# ASP_LEDBoard.net
KiCad netlist of a schematic drawn in Altium Designer
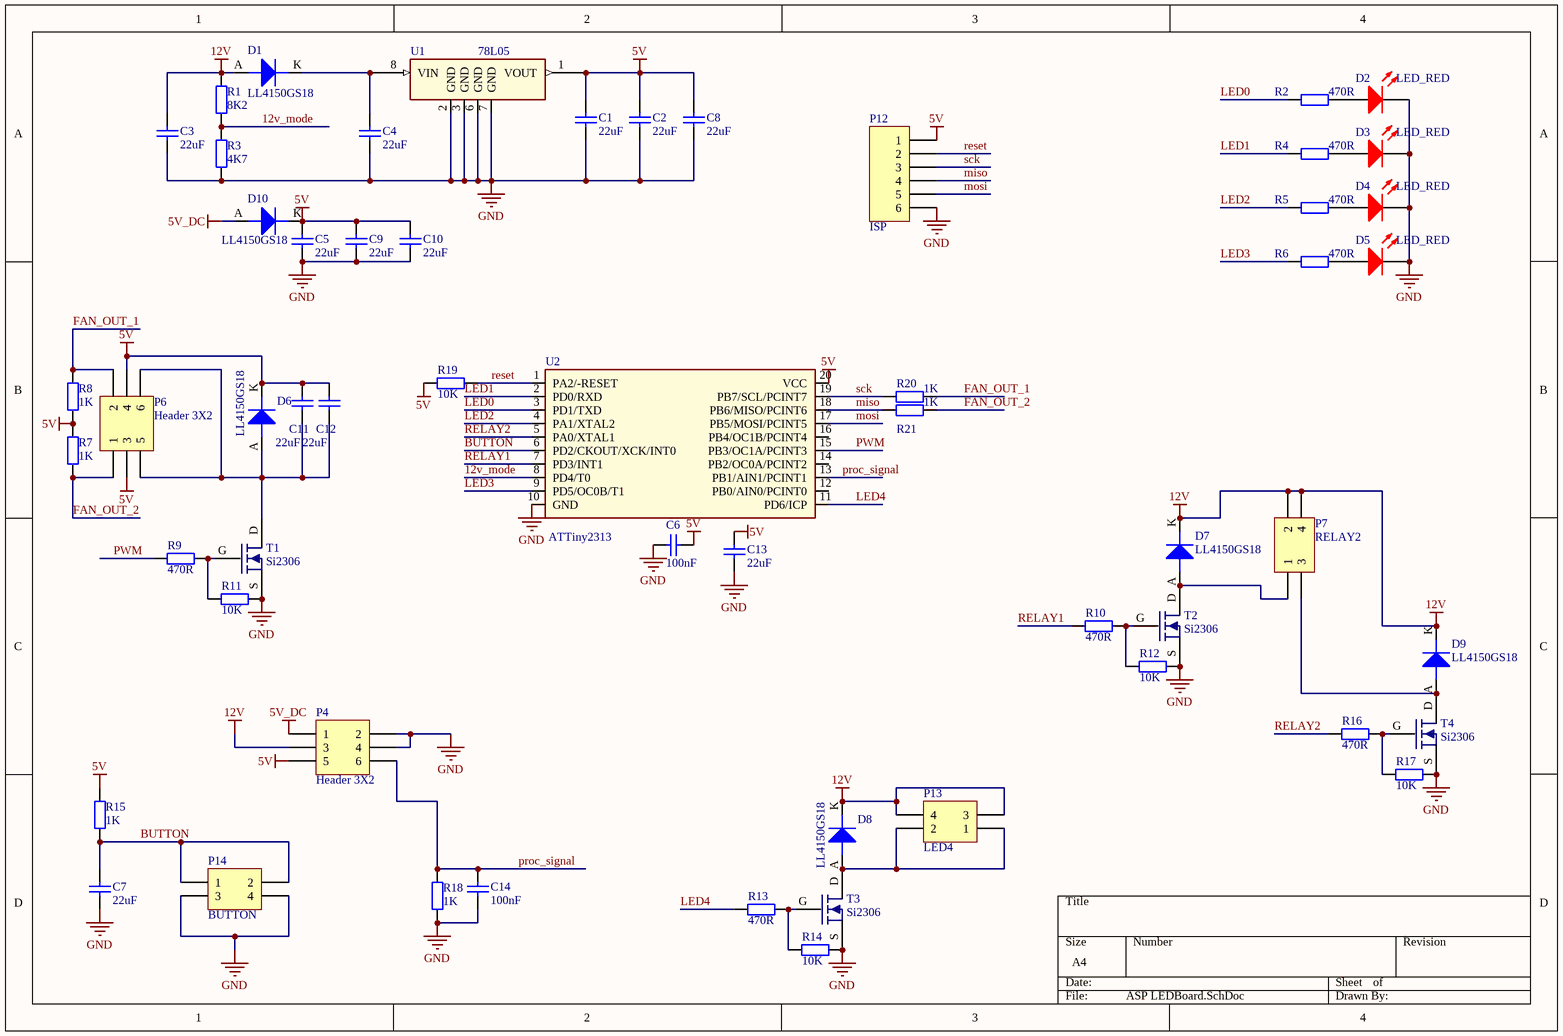
[diagram p0: ASP LEDBoard.SchDoc]

(export (version "E")
  (design (tool "Eeschema 10.0.6"))
  (components
    (comp (ref "C1")
      (value "22uF")
      (footprint "FP_0805_CAP_085")
      (description "Capacitor")
      (libsource (lib "Capacitor") (part "CAP"))
    )
    (comp (ref "C2")
      (value "22uF")
      (footprint "FP_0805_CAP_085")
      (description "Capacitor")
      (libsource (lib "Capacitor") (part "CAP"))
    )
    (comp (ref "C3")
      (value "22uF")
      (footprint "FP_0805_CAP_085")
      (description "Capacitor")
      (libsource (lib "Capacitor") (part "CAP"))
    )
    (comp (ref "C4")
      (value "22uF")
      (footprint "FP_0805_CAP_085")
      (description "Capacitor")
      (libsource (lib "Capacitor") (part "CAP"))
    )
    (comp (ref "C5")
      (value "22uF")
      (footprint "FP_0805_CAP_085")
      (description "Capacitor")
      (libsource (lib "Capacitor") (part "CAP"))
    )
    (comp (ref "C6")
      (value "100nF")
      (footprint "FP_0805_CAP_085")
      (description "Capacitor")
      (libsource (lib "Capacitor") (part "CAP"))
    )
    (comp (ref "C7")
      (value "22uF")
      (footprint "FP_0805_CAP_085")
      (description "Capacitor")
      (libsource (lib "Capacitor") (part "CAP"))
    )
    (comp (ref "C8")
      (value "22uF")
      (footprint "FP_0805_CAP_085")
      (description "Capacitor")
      (libsource (lib "Capacitor") (part "CAP"))
    )
    (comp (ref "C9")
      (value "22uF")
      (footprint "FP_0805_CAP_085")
      (description "Capacitor")
      (libsource (lib "Capacitor") (part "CAP"))
    )
    (comp (ref "C10")
      (value "22uF")
      (footprint "FP_0805_CAP_085")
      (description "Capacitor")
      (libsource (lib "Capacitor") (part "CAP"))
    )
    (comp (ref "C11")
      (value "22uF")
      (footprint "FP_0805_CAP_085")
      (description "Capacitor")
      (libsource (lib "Capacitor") (part "CAP"))
    )
    (comp (ref "C12")
      (value "22uF")
      (footprint "FP_0805_CAP_085")
      (description "Capacitor")
      (libsource (lib "Capacitor") (part "CAP"))
    )
    (comp (ref "C13")
      (value "22uF")
      (footprint "FP_0805_CAP_085")
      (description "Capacitor")
      (libsource (lib "Capacitor") (part "CAP"))
    )
    (comp (ref "C14")
      (value "100nF")
      (footprint "FP_0805_CAP_085")
      (description "Capacitor")
      (libsource (lib "Capacitor") (part "CAP"))
    )
    (comp (ref "D1") (value "LL4150GS18") (footprint "SOD-80") (libsource (lib "Diode") (part "DIODE_big")))
    (comp (ref "D2")
      (value "LED_RED")
      (footprint "1206 LED Reversed")
      (description "Typical LED")
      (libsource (lib "Led_optical") (part "LED_R"))
    )
    (comp (ref "D3")
      (value "LED_RED")
      (footprint "1206 LED Reversed")
      (description "Typical LED")
      (libsource (lib "Led_optical") (part "LED_R"))
    )
    (comp (ref "D4")
      (value "LED_RED")
      (footprint "1206 LED Reversed")
      (description "Typical LED")
      (libsource (lib "Led_optical") (part "LED_R"))
    )
    (comp (ref "D5")
      (value "LED_RED")
      (footprint "1206 LED Reversed")
      (description "Typical LED")
      (libsource (lib "Led_optical") (part "LED_R"))
    )
    (comp (ref "D6") (value "LL4150GS18") (footprint "SOD-80") (libsource (lib "Diode") (part "DIODE_big")))
    (comp (ref "D7") (value "LL4150GS18") (footprint "SOD-80") (libsource (lib "Diode") (part "DIODE_big")))
    (comp (ref "D8") (value "LL4150GS18") (footprint "SOD-80") (libsource (lib "Diode") (part "DIODE_big")))
    (comp (ref "D9") (value "LL4150GS18") (footprint "SOD-80") (libsource (lib "Diode") (part "DIODE_big")))
    (comp (ref "D10") (value "LL4150GS18") (footprint "SOD-80") (libsource (lib "Diode") (part "DIODE_big")))
    (comp (ref "P4")
      (value "Header 3X2")
      (footprint "FP_CONN6_2TUSKE_254MM_smd")
      (description "Header, 3-Pin, Dual row")
      (fields (field (name "PUBLISHER") "Altium Limited"))
      (libsource (lib "") (part "Header 3X2_1"))
    )
    (comp (ref "P6")
      (value "Header 3X2")
      (footprint "FP_CONN6_2TUSKE_254MM_smd")
      (description "Header, 3-Pin, Dual row")
      (fields (field (name "PUBLISHER") "Altium Limited"))
      (libsource (lib "Miscellaneous Connectors") (part "Header 3X2"))
    )
    (comp (ref "P7")
      (value "RELAY2")
      (footprint "FP_CONN4_2TUSKE_254MM_smd")
      (description "Header, 2-Pin, Dual row, Right Angle")
      (fields (field (name "PUBLISHER") "Altium Limited"))
      (libsource (lib "Miscellaneous Connectors") (part "Header 2X2H"))
    )
    (comp (ref "P12")
      (value "ISP")
      (footprint "HDR1X6")
      (description "Header, 6-Pin")
      (fields (field (name "PUBLISHER") "Altium Limited"))
      (libsource (lib "Miscellaneous Connectors") (part "Header 6"))
    )
    (comp (ref "P13")
      (value "LED4")
      (footprint "FP_CONN4_2TUSKE_254MM_smd")
      (description "Header, 2-Pin, Dual row, Right Angle")
      (fields (field (name "PUBLISHER") "Altium Limited"))
      (libsource (lib "") (part "Header 2X2H_2"))
    )
    (comp (ref "P14")
      (value "BUTTON")
      (footprint "FP_CONN4_2TUSKE_254MM_smd")
      (description "Header, 2-Pin, Dual row, Right Angle")
      (fields (field (name "PUBLISHER") "Altium Limited"))
      (libsource (lib "") (part "Header 2X2H_1"))
    )
    (comp (ref "R1")
      (value "8K2")
      (footprint "FP_0805_RES")
      (description "Resistor")
      (libsource (lib "") (part "RES_2"))
    )
    (comp (ref "R2")
      (value "470R")
      (footprint "FP_0805_RES")
      (description "Resistor")
      (libsource (lib "Resistor") (part "RES"))
    )
    (comp (ref "R3")
      (value "4K7")
      (footprint "FP_0805_RES")
      (description "Resistor")
      (libsource (lib "") (part "RES_1"))
    )
    (comp (ref "R4")
      (value "470R")
      (footprint "FP_0805_RES")
      (description "Resistor")
      (libsource (lib "Resistor") (part "RES"))
    )
    (comp (ref "R5")
      (value "470R")
      (footprint "FP_0805_RES")
      (description "Resistor")
      (libsource (lib "Resistor") (part "RES"))
    )
    (comp (ref "R6")
      (value "470R")
      (footprint "FP_0805_RES")
      (description "Resistor")
      (libsource (lib "Resistor") (part "RES"))
    )
    (comp (ref "R7")
      (value "1K")
      (footprint "FP_0805_RES")
      (description "Resistor")
      (libsource (lib "") (part "RES_2"))
    )
    (comp (ref "R8")
      (value "1K")
      (footprint "FP_0805_RES")
      (description "Resistor")
      (libsource (lib "") (part "RES_2"))
    )
    (comp (ref "R9")
      (value "470R")
      (footprint "FP_0805_RES")
      (description "Resistor")
      (libsource (lib "Resistor") (part "RES"))
    )
    (comp (ref "R10")
      (value "470R")
      (footprint "FP_0805_RES")
      (description "Resistor")
      (libsource (lib "Resistor") (part "RES"))
    )
    (comp (ref "R11")
      (value "10K")
      (footprint "FP_0805_RES")
      (description "Resistor")
      (libsource (lib "Resistor") (part "RES"))
    )
    (comp (ref "R12")
      (value "10K")
      (footprint "FP_0805_RES")
      (description "Resistor")
      (libsource (lib "Resistor") (part "RES"))
    )
    (comp (ref "R13")
      (value "470R")
      (footprint "FP_0805_RES")
      (description "Resistor")
      (libsource (lib "Resistor") (part "RES"))
    )
    (comp (ref "R14")
      (value "10K")
      (footprint "FP_0805_RES")
      (description "Resistor")
      (libsource (lib "Resistor") (part "RES"))
    )
    (comp (ref "R15")
      (value "1K")
      (footprint "FP_0805_RES")
      (description "Resistor")
      (libsource (lib "") (part "RES_2"))
    )
    (comp (ref "R16")
      (value "470R")
      (footprint "FP_0805_RES")
      (description "Resistor")
      (libsource (lib "Resistor") (part "RES"))
    )
    (comp (ref "R17")
      (value "10K")
      (footprint "FP_0805_RES")
      (description "Resistor")
      (libsource (lib "Resistor") (part "RES"))
    )
    (comp (ref "R18")
      (value "1K")
      (footprint "FP_0805_RES")
      (description "Resistor")
      (libsource (lib "") (part "RES_1"))
    )
    (comp (ref "R19")
      (value "10K")
      (footprint "FP_0805_RES")
      (description "Resistor")
      (libsource (lib "Resistor") (part "RES"))
    )
    (comp (ref "R20")
      (value "1K")
      (footprint "FP_0805_RES")
      (description "Resistor")
      (libsource (lib "Resistor") (part "RES"))
    )
    (comp (ref "R21")
      (value "1K")
      (footprint "FP_0805_RES")
      (description "Resistor")
      (libsource (lib "Resistor") (part "RES"))
    )
    (comp (ref "T1") (value "Si2306") (footprint "FET_SOT23") (libsource (lib "FET") (part "NMOS")))
    (comp (ref "T2") (value "Si2306") (footprint "FET_SOT23") (libsource (lib "FET") (part "NMOS")))
    (comp (ref "T3") (value "Si2306") (footprint "FET_SOT23") (libsource (lib "FET") (part "NMOS")))
    (comp (ref "T4") (value "Si2306") (footprint "FET_SOT23") (libsource (lib "FET") (part "NMOS")))
    (comp (ref "U1")
      (value "78L05")
      (footprint "Supply_SOIC8")
      (libsource (lib "Supply") (part "78Lxx_SOIC"))
    )
    (comp (ref "U2")
      (value "ATTiny2313")
      (footprint "DIGITAL_SOIC20W")
      (libsource (lib "uC") (part "ATTiny2313"))
    )
  )
  (nets
    (net (code "1") (name "/12v_mode") (class "Default")
      (node (ref "R1") (pin "1") (pinfunction "1_1") (pintype "passive"))
      (node (ref "R3") (pin "1") (pinfunction "1_1") (pintype "passive"))
      (node (ref "U2") (pin "8") (pinfunction "PD4/T0_8") (pintype "passive"))
    )
    (net (code "2") (name "/BUTTON") (class "Default")
      (node (ref "C7") (pin "2") (pinfunction "2_2") (pintype "passive"))
      (node (ref "P14") (pin "1") (pinfunction "1_1") (pintype "passive"))
      (node (ref "P14") (pin "2") (pinfunction "2_2") (pintype "passive"))
      (node (ref "R15") (pin "1") (pinfunction "1_1") (pintype "passive"))
      (node (ref "U2") (pin "6") (pinfunction "PD2/CKOUT/XCK/INT0_6") (pintype "passive"))
    )
    (net (code "3") (name "/FAN_OUT_1") (class "Default")
      (node (ref "P6") (pin "2") (pinfunction "2_2") (pintype "passive"))
      (node (ref "R20") (pin "1") (pinfunction "1_1") (pintype "passive"))
      (node (ref "R8") (pin "2") (pinfunction "2_2") (pintype "passive"))
    )
    (net (code "4") (name "/FAN_OUT_2") (class "Default")
      (node (ref "P6") (pin "1") (pinfunction "1_1") (pintype "passive"))
      (node (ref "R21") (pin "1") (pinfunction "1_1") (pintype "passive"))
      (node (ref "R7") (pin "1") (pinfunction "1_1") (pintype "passive"))
    )
    (net (code "5") (name "/LED0") (class "Default")
      (node (ref "R2") (pin "2") (pinfunction "2_2") (pintype "passive"))
      (node (ref "U2") (pin "3") (pinfunction "PD1/TXD_3") (pintype "passive"))
    )
    (net (code "6") (name "/LED1") (class "Default")
      (node (ref "R4") (pin "2") (pinfunction "2_2") (pintype "passive"))
      (node (ref "U2") (pin "2") (pinfunction "PD0/RXD_2") (pintype "passive"))
    )
    (net (code "7") (name "/LED2") (class "Default")
      (node (ref "R5") (pin "2") (pinfunction "2_2") (pintype "passive"))
      (node (ref "U2") (pin "4") (pinfunction "PA1/XTAL2_4") (pintype "passive"))
    )
    (net (code "8") (name "/LED3") (class "Default")
      (node (ref "R6") (pin "2") (pinfunction "2_2") (pintype "passive"))
      (node (ref "U2") (pin "9") (pinfunction "PD5/OC0B/T1_9") (pintype "passive"))
    )
    (net (code "9") (name "/LED4") (class "Default")
      (node (ref "R13") (pin "2") (pinfunction "2_2") (pintype "passive"))
      (node (ref "U2") (pin "11") (pinfunction "PD6/ICP_11") (pintype "passive"))
    )
    (net (code "10") (name "/PWM") (class "Default")
      (node (ref "R9") (pin "2") (pinfunction "2_2") (pintype "passive"))
      (node (ref "U2") (pin "15") (pinfunction "PB3/OC1A/PCINT3_15") (pintype "passive"))
    )
    (net (code "11") (name "/RELAY1") (class "Default")
      (node (ref "R10") (pin "2") (pinfunction "2_2") (pintype "passive"))
      (node (ref "U2") (pin "7") (pinfunction "PD3/INT1_7") (pintype "passive"))
    )
    (net (code "12") (name "/RELAY2") (class "Default")
      (node (ref "R16") (pin "2") (pinfunction "2_2") (pintype "passive"))
      (node (ref "U2") (pin "5") (pinfunction "PA0/XTAL1_5") (pintype "passive"))
    )
    (net (code "13") (name "/miso") (class "Default")
      (node (ref "P12") (pin "4") (pinfunction "4_4") (pintype "passive"))
      (node (ref "R21") (pin "2") (pinfunction "2_2") (pintype "passive"))
      (node (ref "U2") (pin "18") (pinfunction "PB6/MISO/PCINT6_18") (pintype "passive"))
    )
    (net (code "14") (name "/mosi") (class "Default")
      (node (ref "P12") (pin "5") (pinfunction "5_5") (pintype "passive"))
      (node (ref "U2") (pin "17") (pinfunction "PB5/MOSI/PCINT5_17") (pintype "passive"))
    )
    (net (code "15") (name "/proc_signal") (class "Default")
      (node (ref "C14") (pin "2") (pinfunction "2_2") (pintype "passive"))
      (node (ref "P4") (pin "6") (pinfunction "6_6") (pintype "passive"))
      (node (ref "R18") (pin "1") (pinfunction "1_1") (pintype "passive"))
      (node (ref "U2") (pin "13") (pinfunction "PB1/AIN1/PCINT1_13") (pintype "passive"))
    )
    (net (code "16") (name "/reset") (class "Default")
      (node (ref "P12") (pin "2") (pinfunction "2_2") (pintype "passive"))
      (node (ref "R19") (pin "1") (pinfunction "1_1") (pintype "passive"))
      (node (ref "U2") (pin "1") (pinfunction "PA2/-RESET_1") (pintype "passive"))
    )
    (net (code "17") (name "/sck") (class "Default")
      (node (ref "P12") (pin "3") (pinfunction "3_3") (pintype "passive"))
      (node (ref "R20") (pin "2") (pinfunction "2_2") (pintype "passive"))
      (node (ref "U2") (pin "19") (pinfunction "PB7/SCL/PCINT7_19") (pintype "passive"))
    )
    (net (code "18") (name "5V") (class "Default")
      (node (ref "C1") (pin "2") (pinfunction "2_2") (pintype "passive"))
      (node (ref "C10") (pin "2") (pinfunction "2_2") (pintype "passive"))
      (node (ref "C11") (pin "2") (pinfunction "2_2") (pintype "passive"))
      (node (ref "C12") (pin "2") (pinfunction "2_2") (pintype "passive"))
      (node (ref "C13") (pin "2") (pinfunction "2_2") (pintype "passive"))
      (node (ref "C2") (pin "2") (pinfunction "2_2") (pintype "passive"))
      (node (ref "C5") (pin "2") (pinfunction "2_2") (pintype "passive"))
      (node (ref "C6") (pin "2") (pinfunction "2_2") (pintype "passive"))
      (node (ref "C8") (pin "2") (pinfunction "2_2") (pintype "passive"))
      (node (ref "C9") (pin "2") (pinfunction "2_2") (pintype "passive"))
      (node (ref "D10") (pin "K") (pinfunction "K_K") (pintype "passive"))
      (node (ref "D6") (pin "K") (pinfunction "K_K") (pintype "passive"))
      (node (ref "P12") (pin "1") (pinfunction "1_1") (pintype "passive"))
      (node (ref "P4") (pin "5") (pinfunction "5_5") (pintype "passive"))
      (node (ref "P6") (pin "3") (pinfunction "3_3") (pintype "passive"))
      (node (ref "P6") (pin "4") (pinfunction "4_4") (pintype "passive"))
      (node (ref "R15") (pin "2") (pinfunction "2_2") (pintype "passive"))
      (node (ref "R19") (pin "2") (pinfunction "2_2") (pintype "passive"))
      (node (ref "R7") (pin "2") (pinfunction "2_2") (pintype "passive"))
      (node (ref "R8") (pin "1") (pinfunction "1_1") (pintype "passive"))
      (node (ref "U1") (pin "1") (pinfunction "VOUT_1") (pintype "output"))
      (node (ref "U2") (pin "20") (pinfunction "VCC_20") (pintype "passive"))
    )
    (net (code "19") (name "5V_DC") (class "Default")
      (node (ref "D10") (pin "A") (pinfunction "A_A") (pintype "passive"))
      (node (ref "P4") (pin "1") (pinfunction "1_1") (pintype "passive"))
    )
    (net (code "20") (name "12V") (class "Default")
      (node (ref "C3") (pin "2") (pinfunction "2_2") (pintype "passive"))
      (node (ref "D1") (pin "A") (pinfunction "A_A") (pintype "passive"))
      (node (ref "D7") (pin "K") (pinfunction "K_K") (pintype "passive"))
      (node (ref "D8") (pin "K") (pinfunction "K_K") (pintype "passive"))
      (node (ref "D9") (pin "K") (pinfunction "K_K") (pintype "passive"))
      (node (ref "P13") (pin "3") (pinfunction "3_3") (pintype "passive"))
      (node (ref "P13") (pin "4") (pinfunction "4_4") (pintype "passive"))
      (node (ref "P4") (pin "3") (pinfunction "3_3") (pintype "passive"))
      (node (ref "P7") (pin "2") (pinfunction "2_2") (pintype "passive"))
      (node (ref "P7") (pin "4") (pinfunction "4_4") (pintype "passive"))
      (node (ref "R1") (pin "2") (pinfunction "2_2") (pintype "passive"))
    )
    (net (code "21") (name "GND") (class "Default")
      (node (ref "C1") (pin "1") (pinfunction "1_1") (pintype "passive"))
      (node (ref "C10") (pin "1") (pinfunction "1_1") (pintype "passive"))
      (node (ref "C13") (pin "1") (pinfunction "1_1") (pintype "passive"))
      (node (ref "C14") (pin "1") (pinfunction "1_1") (pintype "passive"))
      (node (ref "C2") (pin "1") (pinfunction "1_1") (pintype "passive"))
      (node (ref "C3") (pin "1") (pinfunction "1_1") (pintype "passive"))
      (node (ref "C4") (pin "1") (pinfunction "1_1") (pintype "passive"))
      (node (ref "C5") (pin "1") (pinfunction "1_1") (pintype "passive"))
      (node (ref "C6") (pin "1") (pinfunction "1_1") (pintype "passive"))
      (node (ref "C7") (pin "1") (pinfunction "1_1") (pintype "passive"))
      (node (ref "C8") (pin "1") (pinfunction "1_1") (pintype "passive"))
      (node (ref "C9") (pin "1") (pinfunction "1_1") (pintype "passive"))
      (node (ref "D2") (pin "K") (pinfunction "K_K") (pintype "passive"))
      (node (ref "D3") (pin "K") (pinfunction "K_K") (pintype "passive"))
      (node (ref "D4") (pin "K") (pinfunction "K_K") (pintype "passive"))
      (node (ref "D5") (pin "K") (pinfunction "K_K") (pintype "passive"))
      (node (ref "P12") (pin "6") (pinfunction "6_6") (pintype "passive"))
      (node (ref "P14") (pin "3") (pinfunction "3_3") (pintype "passive"))
      (node (ref "P14") (pin "4") (pinfunction "4_4") (pintype "passive"))
      (node (ref "P4") (pin "2") (pinfunction "2_2") (pintype "passive"))
      (node (ref "P4") (pin "4") (pinfunction "4_4") (pintype "passive"))
      (node (ref "R11") (pin "1") (pinfunction "1_1") (pintype "passive"))
      (node (ref "R12") (pin "1") (pinfunction "1_1") (pintype "passive"))
      (node (ref "R14") (pin "1") (pinfunction "1_1") (pintype "passive"))
      (node (ref "R17") (pin "1") (pinfunction "1_1") (pintype "passive"))
      (node (ref "R18") (pin "2") (pinfunction "2_2") (pintype "passive"))
      (node (ref "R3") (pin "2") (pinfunction "2_2") (pintype "passive"))
      (node (ref "T1") (pin "S") (pinfunction "S_S") (pintype "passive"))
      (node (ref "T2") (pin "S") (pinfunction "S_S") (pintype "passive"))
      (node (ref "T3") (pin "S") (pinfunction "S_S") (pintype "passive"))
      (node (ref "T4") (pin "S") (pinfunction "S_S") (pintype "passive"))
      (node (ref "U1") (pin "2") (pinfunction "GND_2") (pintype "power_in"))
      (node (ref "U1") (pin "3") (pinfunction "GND_3") (pintype "power_in"))
      (node (ref "U1") (pin "6") (pinfunction "GND_6") (pintype "power_in"))
      (node (ref "U1") (pin "7") (pinfunction "GND_7") (pintype "power_in"))
      (node (ref "U2") (pin "10") (pinfunction "GND_10") (pintype "passive"))
    )
    (net (code "22") (name "Net-(C11-Pad1)") (class "Default")
      (node (ref "C11") (pin "1") (pinfunction "1_1") (pintype "passive"))
      (node (ref "C12") (pin "1") (pinfunction "1_1") (pintype "passive"))
      (node (ref "D6") (pin "A") (pinfunction "A_A") (pintype "passive"))
      (node (ref "P6") (pin "5") (pinfunction "5_5") (pintype "passive"))
      (node (ref "P6") (pin "6") (pinfunction "6_6") (pintype "passive"))
      (node (ref "T1") (pin "D") (pinfunction "D_D") (pintype "passive"))
    )
    (net (code "23") (name "Net-(D2-PadA)") (class "Default")
      (node (ref "D2") (pin "A") (pinfunction "A_A") (pintype "passive"))
      (node (ref "R2") (pin "1") (pinfunction "1_1") (pintype "passive"))
    )
    (net (code "24") (name "Net-(D3-PadA)") (class "Default")
      (node (ref "D3") (pin "A") (pinfunction "A_A") (pintype "passive"))
      (node (ref "R4") (pin "1") (pinfunction "1_1") (pintype "passive"))
    )
    (net (code "25") (name "Net-(D4-PadA)") (class "Default")
      (node (ref "D4") (pin "A") (pinfunction "A_A") (pintype "passive"))
      (node (ref "R5") (pin "1") (pinfunction "1_1") (pintype "passive"))
    )
    (net (code "26") (name "Net-(D5-PadA)") (class "Default")
      (node (ref "D5") (pin "A") (pinfunction "A_A") (pintype "passive"))
      (node (ref "R6") (pin "1") (pinfunction "1_1") (pintype "passive"))
    )
    (net (code "27") (name "Net-(D7-PadA)") (class "Default")
      (node (ref "D7") (pin "A") (pinfunction "A_A") (pintype "passive"))
      (node (ref "P7") (pin "1") (pinfunction "1_1") (pintype "passive"))
      (node (ref "T2") (pin "D") (pinfunction "D_D") (pintype "passive"))
    )
    (net (code "28") (name "Net-(D8-PadA)") (class "Default")
      (node (ref "D8") (pin "A") (pinfunction "A_A") (pintype "passive"))
      (node (ref "P13") (pin "1") (pinfunction "1_1") (pintype "passive"))
      (node (ref "P13") (pin "2") (pinfunction "2_2") (pintype "passive"))
      (node (ref "T3") (pin "D") (pinfunction "D_D") (pintype "passive"))
    )
    (net (code "29") (name "Net-(D9-PadA)") (class "Default")
      (node (ref "D9") (pin "A") (pinfunction "A_A") (pintype "passive"))
      (node (ref "P7") (pin "3") (pinfunction "3_3") (pintype "passive"))
      (node (ref "T4") (pin "D") (pinfunction "D_D") (pintype "passive"))
    )
    (net (code "30") (name "Net-(R10-Pad1)") (class "Default")
      (node (ref "R10") (pin "1") (pinfunction "1_1") (pintype "passive"))
      (node (ref "R12") (pin "2") (pinfunction "2_2") (pintype "passive"))
      (node (ref "T2") (pin "G") (pinfunction "G_G") (pintype "passive"))
    )
    (net (code "31") (name "Net-(R11-Pad2)") (class "Default")
      (node (ref "R11") (pin "2") (pinfunction "2_2") (pintype "passive"))
      (node (ref "R9") (pin "1") (pinfunction "1_1") (pintype "passive"))
      (node (ref "T1") (pin "G") (pinfunction "G_G") (pintype "passive"))
    )
    (net (code "32") (name "Net-(R13-Pad1)") (class "Default")
      (node (ref "R13") (pin "1") (pinfunction "1_1") (pintype "passive"))
      (node (ref "R14") (pin "2") (pinfunction "2_2") (pintype "passive"))
      (node (ref "T3") (pin "G") (pinfunction "G_G") (pintype "passive"))
    )
    (net (code "33") (name "Net-(R16-Pad1)") (class "Default")
      (node (ref "R16") (pin "1") (pinfunction "1_1") (pintype "passive"))
      (node (ref "R17") (pin "2") (pinfunction "2_2") (pintype "passive"))
      (node (ref "T4") (pin "G") (pinfunction "G_G") (pintype "passive"))
    )
    (net (code "34") (name "Net-(U1-VIN)") (class "Default")
      (node (ref "C4") (pin "2") (pinfunction "2_2") (pintype "passive"))
      (node (ref "D1") (pin "K") (pinfunction "K_K") (pintype "passive"))
      (node (ref "U1") (pin "8") (pinfunction "VIN_8") (pintype "input"))
    )
    (net (code "35") (name "unconnected-(U2-PB0{slash}AIN0{slash}PCINT0-Pad12)") (class "Default")
      (node (ref "U2") (pin "12") (pinfunction "PB0/AIN0/PCINT0_12") (pintype "passive"))
    )
    (net (code "36") (name "unconnected-(U2-PB2{slash}OC0A{slash}PCINT2-Pad14)") (class "Default")
      (node (ref "U2") (pin "14") (pinfunction "PB2/OC0A/PCINT2_14") (pintype "passive"))
    )
    (net (code "37") (name "unconnected-(U2-PB4{slash}OC1B{slash}PCINT4-Pad16)") (class "Default")
      (node (ref "U2") (pin "16") (pinfunction "PB4/OC1B/PCINT4_16") (pintype "passive"))
    )
  )
)
